# schematic.net
KiCad netlist of a schematic drawn in EasyEDA
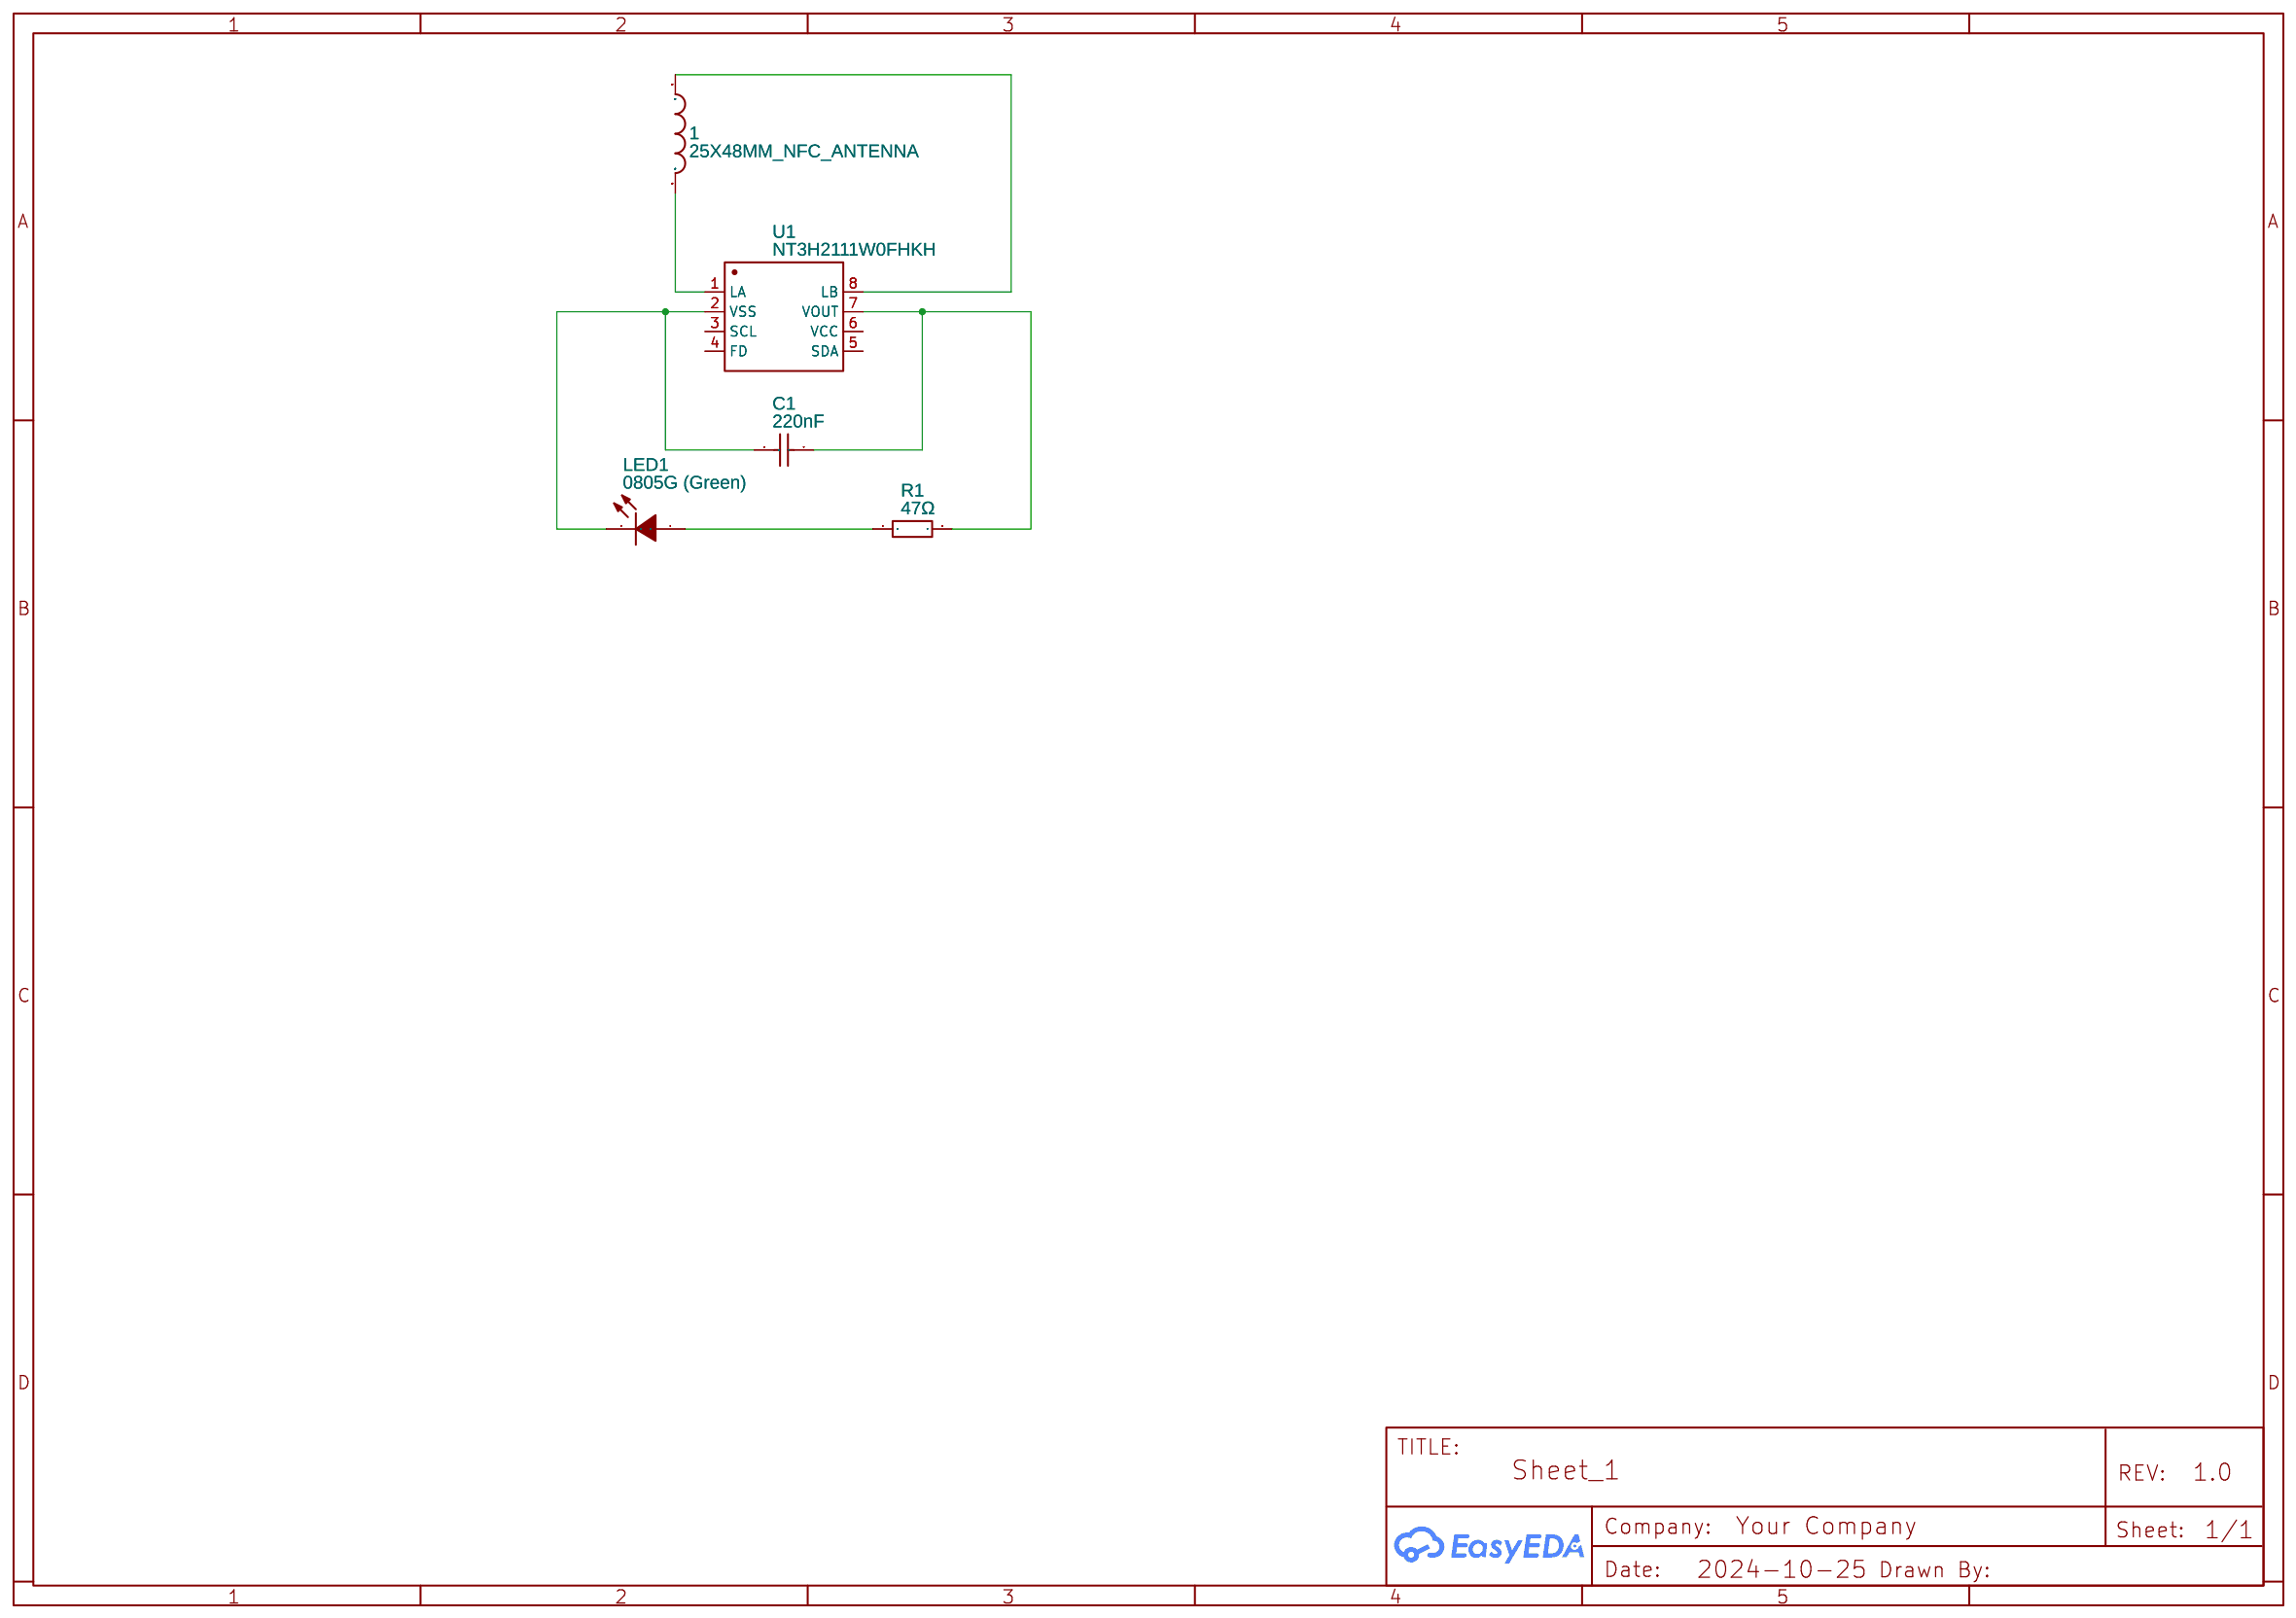
[diagram p0: schematic sheet]

(export (version "E")
  (design (tool "Eeschema 10.0.6"))
  (components
    (comp (ref "1") (value "25X48MM_NFC_ANTENNA") (libsource (lib "") (part "25X48MM_NFC_ANTENNA")))
    (comp (ref "C1")
      (value "220nF")
      (fields
        (field (name "Manufacturer Part") "CL10B224KA8NNNC")
        (field (name "Manufacturer") "SAMSUNG(三星)")
      )
      (libsource (lib "") (part "CL10B224KA8NNNC"))
    )
    (comp (ref "LED1")
      (value "0805G (Green)")
      (fields (field (name "Manufacturer Part") "KT-0805G") (field (name "Manufacturer") "KENTO"))
      (libsource (lib "") (part "0805G (Green)"))
    )
    (comp (ref "R1")
      (value "47Ω")
      (fields
        (field (name "Manufacturer Part") "0603WAF470JT5E")
        (field (name "Manufacturer") "UNI-ROYAL(厚声)")
      )
      (libsource (lib "") (part "0603WAF470JT5E"))
    )
    (comp (ref "U1")
      (value "NT3H2111W0FHKH")
      (fields (field (name "Manufacturer") "NXP(恩智浦)"))
      (libsource (lib "") (part "NT3H2111W0FHKH"))
    )
  )
  (nets
    (net (code "1") (name "Net-(LED1-A)") (class "Default")
      (node (ref "LED1") (pin "1") (pinfunction "A_1") (pintype "unspecified"))
      (node (ref "R1") (pin "1") (pinfunction "1_1") (pintype "input"))
    )
    (net (code "2") (name "Net-(LED1-K)") (class "Default")
      (node (ref "C1") (pin "1") (pinfunction "1_1") (pintype "input"))
      (node (ref "LED1") (pin "2") (pinfunction "K_2") (pintype "unspecified"))
      (node (ref "U1") (pin "2") (pinfunction "VSS_2") (pintype "unspecified"))
    )
    (net (code "3") (name "Net-(U1-LA)") (class "Default")
      (node (ref "1") (pin "P$2") (pinfunction "P$2_P$2") (pintype "bidirectional"))
      (node (ref "U1") (pin "1") (pinfunction "LA_1") (pintype "unspecified"))
    )
    (net (code "4") (name "Net-(U1-LB)") (class "Default")
      (node (ref "1") (pin "P$1") (pinfunction "P$1_P$1") (pintype "bidirectional"))
      (node (ref "U1") (pin "8") (pinfunction "LB_8") (pintype "unspecified"))
    )
    (net (code "5") (name "Net-(U1-VOUT)") (class "Default")
      (node (ref "C1") (pin "2") (pinfunction "2_2") (pintype "input"))
      (node (ref "R1") (pin "2") (pinfunction "2_2") (pintype "input"))
      (node (ref "U1") (pin "7") (pinfunction "VOUT_7") (pintype "unspecified"))
    )
    (net (code "6") (name "unconnected-(U1-FD-Pad4)") (class "Default")
      (node (ref "U1") (pin "4") (pinfunction "FD_4") (pintype "unspecified"))
    )
    (net (code "7") (name "unconnected-(U1-SCL-Pad3)") (class "Default")
      (node (ref "U1") (pin "3") (pinfunction "SCL_3") (pintype "unspecified"))
    )
    (net (code "8") (name "unconnected-(U1-SDA-Pad5)") (class "Default")
      (node (ref "U1") (pin "5") (pinfunction "SDA_5") (pintype "unspecified"))
    )
    (net (code "9") (name "unconnected-(U1-VCC-Pad6)") (class "Default")
      (node (ref "U1") (pin "6") (pinfunction "VCC_6") (pintype "unspecified"))
    )
  )
)
